# 01_Mcu.net
KiCad netlist of a schematic drawn in Altium Designer
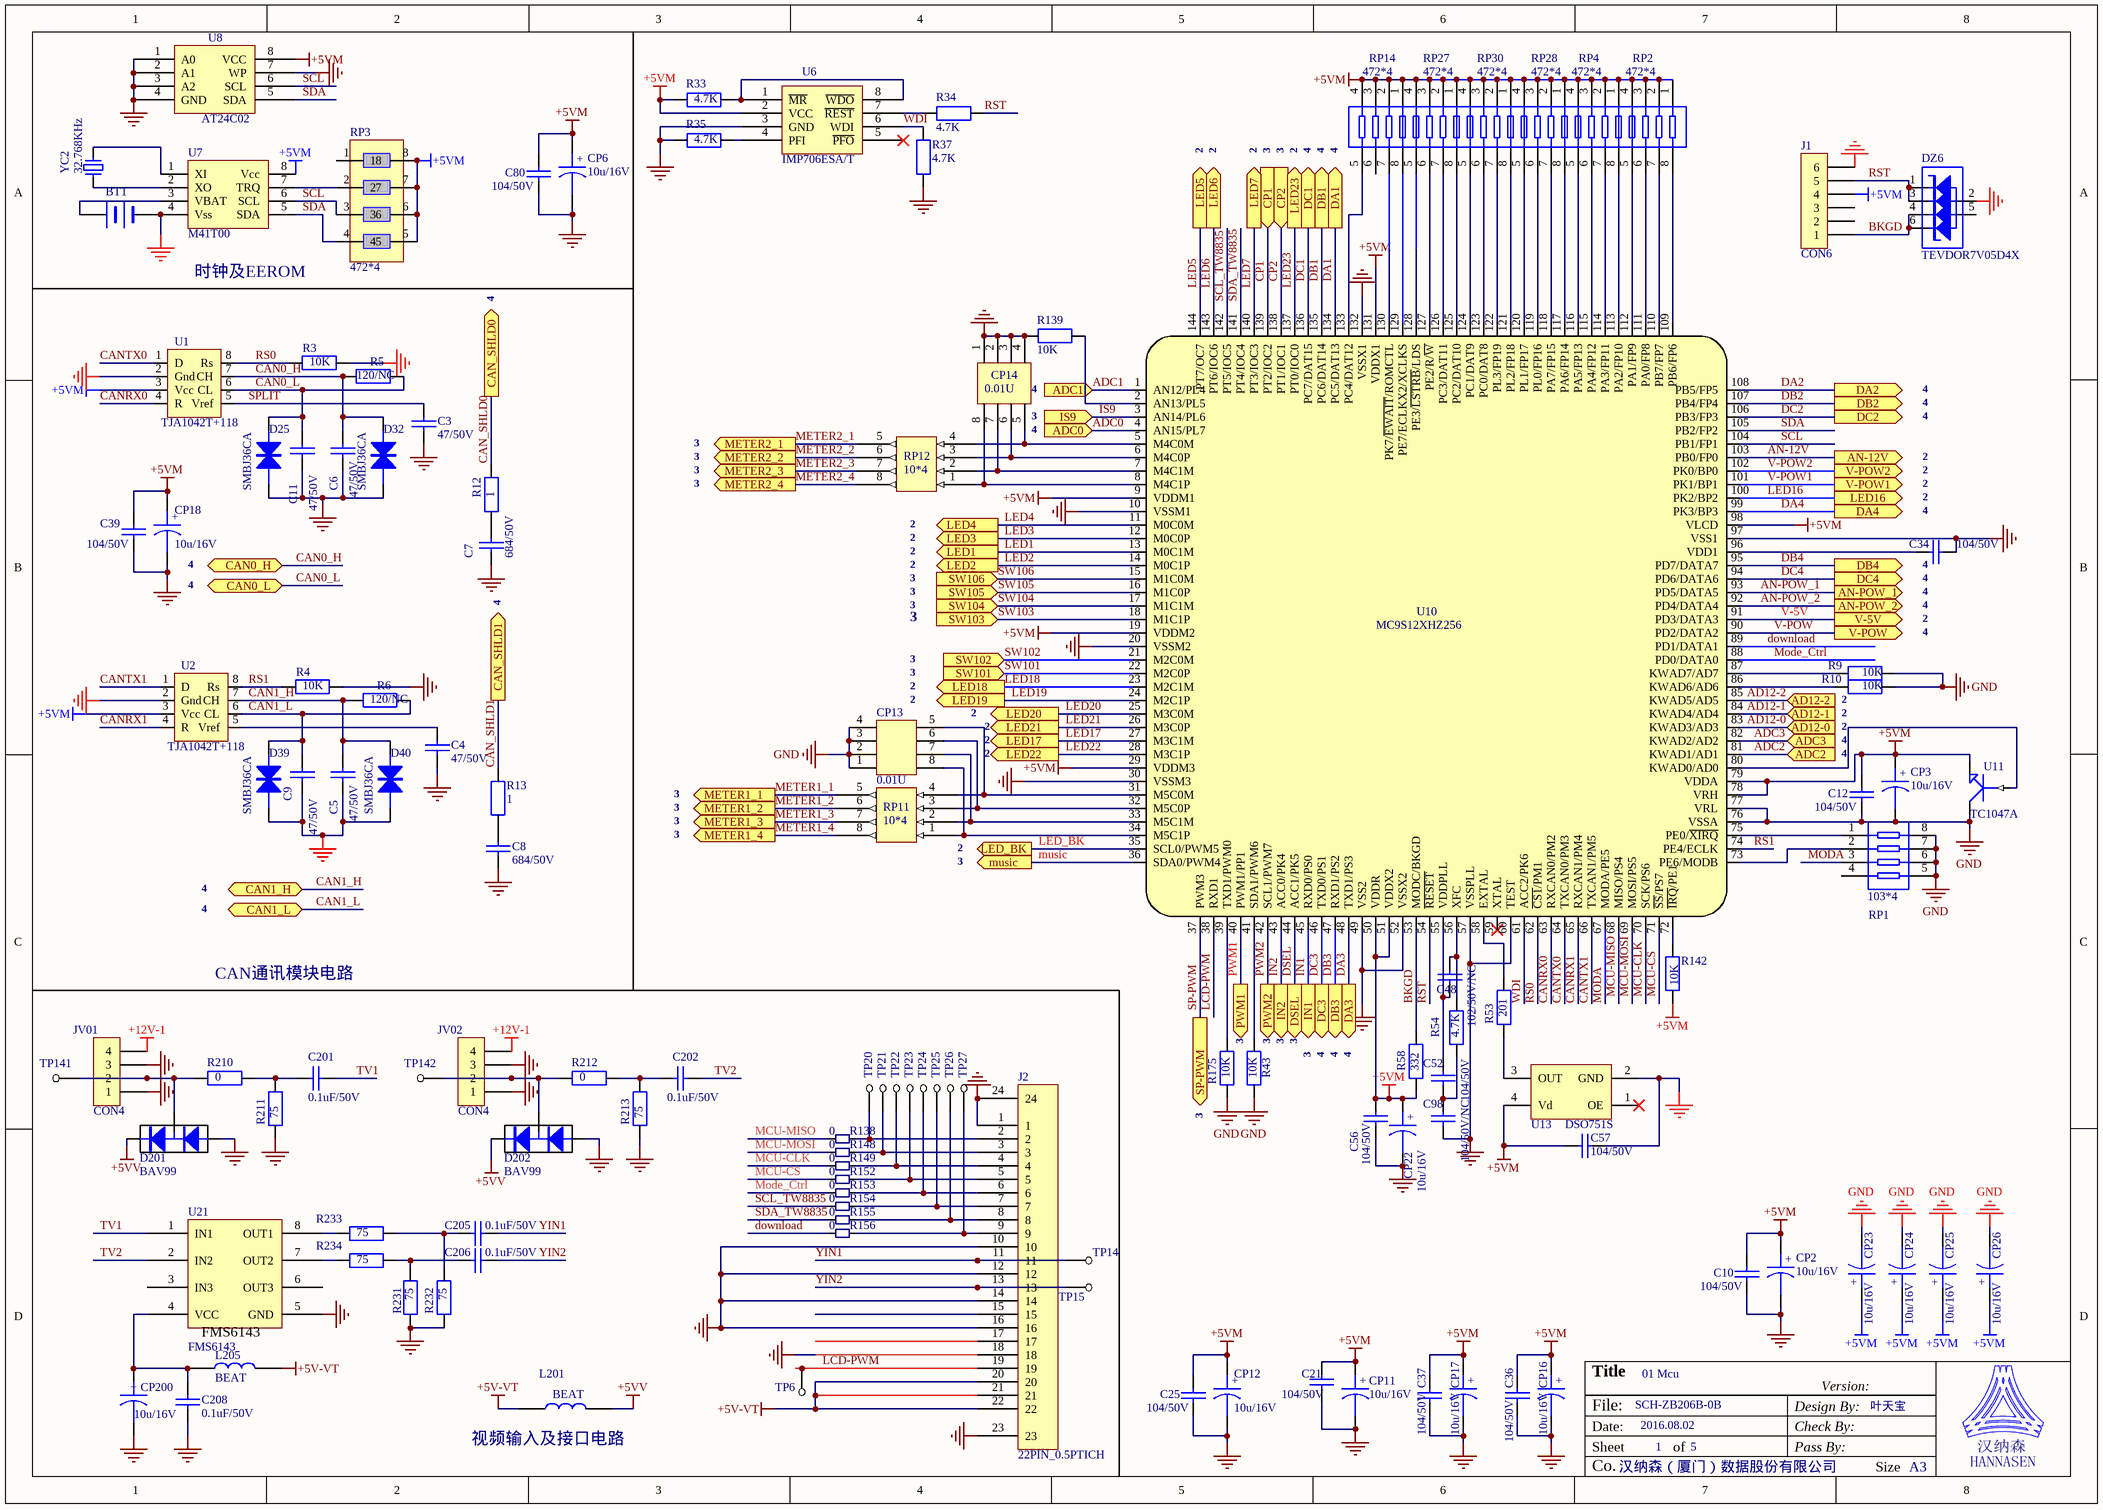
[diagram p0: 01 Mcu.SchDoc]

(export (version "E")
  (design (tool "Eeschema 10.0.6"))
  (components
    (comp (ref "BT1")
      (value "~")
      (footprint "Battery 3")
      (description "Battery")
      (libsource (lib "*") (part "BATTERY"))
    )
    (comp (ref "C3")
      (value "47/50V")
      (footprint "CR0805")
      (description "Capacitor")
      (libsource (lib "*") (part "CAP"))
    )
    (comp (ref "C4")
      (value "47/50V")
      (footprint "CR0805")
      (description "Capacitor")
      (libsource (lib "*") (part "CAP"))
    )
    (comp (ref "C5")
      (value "47/50V")
      (footprint "CR0805")
      (description "Capacitor")
      (libsource (lib "*") (part "CAP"))
    )
    (comp (ref "C6")
      (value "47/50V")
      (footprint "CR0805")
      (description "Capacitor")
      (libsource (lib "*") (part "CAP"))
    )
    (comp (ref "C7")
      (value "684/50V")
      (footprint "CR1206")
      (description "Capacitor")
      (libsource (lib "*") (part "CAP"))
    )
    (comp (ref "C8")
      (value "684/50V")
      (footprint "CR1206")
      (description "Capacitor")
      (libsource (lib "*") (part "CAP"))
    )
    (comp (ref "C9")
      (value "47/50V")
      (footprint "CR0805")
      (description "Capacitor")
      (libsource (lib "*") (part "CAP"))
    )
    (comp (ref "C10")
      (value "104/50V")
      (footprint "CR0805")
      (description "Capacitor")
      (libsource (lib "*") (part "CAP"))
    )
    (comp (ref "C11")
      (value "47/50V")
      (footprint "CR0805")
      (description "Capacitor")
      (libsource (lib "*") (part "CAP"))
    )
    (comp (ref "C12")
      (value "104/50V")
      (footprint "CR0805")
      (description "Capacitor")
      (libsource (lib "*") (part "CAP"))
    )
    (comp (ref "C21")
      (value "104/50V")
      (footprint "CR0805")
      (description "Capacitor")
      (libsource (lib "*") (part "CAP"))
    )
    (comp (ref "C25")
      (value "104/50V")
      (footprint "CR0805")
      (description "Capacitor")
      (libsource (lib "*") (part "CAP"))
    )
    (comp (ref "C34")
      (value "104/50V")
      (footprint "CR0805")
      (description "Capacitor")
      (libsource (lib "*") (part "CAP"))
    )
    (comp (ref "C36")
      (value "104/50V")
      (footprint "CR0805")
      (description "Capacitor")
      (libsource (lib "*") (part "CAP"))
    )
    (comp (ref "C37")
      (value "104/50V")
      (footprint "CR0805")
      (description "Capacitor")
      (libsource (lib "*") (part "CAP"))
    )
    (comp (ref "C39")
      (value "104/50V")
      (footprint "CR0805")
      (description "Capacitor")
      (libsource (lib "*") (part "CAP"))
    )
    (comp (ref "C48")
      (value "102/50V/NC")
      (footprint "CR0805")
      (description "Capacitor")
      (libsource (lib "*") (part "CAP"))
    )
    (comp (ref "C52")
      (value "104/50V")
      (footprint "CR0805")
      (description "Capacitor")
      (libsource (lib "*") (part "CAP"))
    )
    (comp (ref "C56")
      (value "104/50V")
      (footprint "CR0805")
      (description "Capacitor")
      (libsource (lib "*") (part "CAP"))
    )
    (comp (ref "C57")
      (value "104/50V")
      (footprint "CR0805")
      (description "Capacitor")
      (libsource (lib "*") (part "CAP"))
    )
    (comp (ref "C80")
      (value "104/50V")
      (footprint "CR0805")
      (description "Capacitor")
      (libsource (lib "*") (part "CAP"))
    )
    (comp (ref "C98")
      (value "104/50V/NC")
      (footprint "CR0805")
      (description "Capacitor")
      (libsource (lib "*") (part "CAP"))
    )
    (comp (ref "C201")
      (value "0.1uF/50V")
      (footprint "CR0805")
      (description "贴片电容")
      (libsource (lib "YDM-SQ-1SCH") (part "CAP"))
    )
    (comp (ref "C202")
      (value "0.1uF/50V")
      (footprint "CR0805")
      (description "贴片电容")
      (libsource (lib "YDM-SQ-1SCH") (part "CAP"))
    )
    (comp (ref "C205")
      (value "0.1uF/50V")
      (footprint "CR0805")
      (description "贴片电容")
      (libsource (lib "YDM-SQ-1SCH") (part "CAP"))
    )
    (comp (ref "C206")
      (value "0.1uF/50V")
      (footprint "CR0805")
      (description "贴片电容")
      (libsource (lib "YDM-SQ-1SCH") (part "CAP"))
    )
    (comp (ref "C208")
      (value "0.1uF/50V")
      (footprint "CR0805")
      (description "Capacitor")
      (libsource (lib "*") (part "CAP"))
    )
    (comp (ref "CP2")
      (value "10u/16V")
      (footprint "CE1206")
      (description "Capacitor")
      (libsource (lib "*") (part "CAPACITOR POL"))
    )
    (comp (ref "CP3")
      (value "10u/16V")
      (footprint "CE1206")
      (description "Capacitor")
      (libsource (lib "*") (part "CAPACITOR POL"))
    )
    (comp (ref "CP6")
      (value "10u/16V")
      (footprint "CE1206")
      (description "Capacitor")
      (libsource (lib "*") (part "CAPACITOR POL"))
    )
    (comp (ref "CP11")
      (value "10u/16V")
      (footprint "CE1206")
      (description "Capacitor")
      (libsource (lib "*") (part "CAPACITOR POL"))
    )
    (comp (ref "CP12")
      (value "10u/16V")
      (footprint "CE1206")
      (description "Capacitor")
      (libsource (lib "*") (part "CAPACITOR POL"))
    )
    (comp (ref "CP13") (value "0.01U") (footprint "C4") (libsource (lib "*") (part "RC_ARRAY")))
    (comp (ref "CP14") (value "0.01U") (footprint "C4") (libsource (lib "") (part "RC_ARRAY_1")))
    (comp (ref "CP16")
      (value "10u/16V")
      (footprint "CE1206")
      (description "Capacitor")
      (libsource (lib "*") (part "CAPACITOR POL"))
    )
    (comp (ref "CP17")
      (value "10u/16V")
      (footprint "CE1206")
      (description "Capacitor")
      (libsource (lib "*") (part "CAPACITOR POL"))
    )
    (comp (ref "CP18")
      (value "10u/16V")
      (footprint "CE1206")
      (description "Capacitor")
      (libsource (lib "*") (part "CAPACITOR POL"))
    )
    (comp (ref "CP22")
      (value "10u/16V")
      (footprint "CE1206")
      (description "Capacitor")
      (libsource (lib "*") (part "CAPACITOR POL"))
    )
    (comp (ref "CP23")
      (value "10u/16V")
      (footprint "CE1206")
      (description "Capacitor")
      (libsource (lib "*") (part "CAPACITOR POL"))
    )
    (comp (ref "CP24")
      (value "10u/16V")
      (footprint "CE1206")
      (description "Capacitor")
      (libsource (lib "*") (part "CAPACITOR POL"))
    )
    (comp (ref "CP25")
      (value "10u/16V")
      (footprint "CE1206")
      (description "Capacitor")
      (libsource (lib "*") (part "CAPACITOR POL"))
    )
    (comp (ref "CP26")
      (value "10u/16V")
      (footprint "CE1206")
      (description "Capacitor")
      (libsource (lib "*") (part "CAPACITOR POL"))
    )
    (comp (ref "CP200")
      (value "10u/16V")
      (footprint "CE1206")
      (description "Capacitor")
      (libsource (lib "") (part "CAPACITOR POL_1"))
    )
    (comp (ref "D25") (value "SMBJ36CA") (footprint "SMB-D") (libsource (lib "YDM-SQ-1SCH") (part "TVS")))
    (comp (ref "D32") (value "SMBJ36CA") (footprint "SMB-D") (libsource (lib "YDM-SQ-1SCH") (part "TVS")))
    (comp (ref "D39") (value "SMBJ36CA") (footprint "SMB-D") (libsource (lib "YDM-SQ-1SCH") (part "TVS")))
    (comp (ref "D40") (value "SMBJ36CA") (footprint "SMB-D") (libsource (lib "YDM-SQ-1SCH") (part "TVS")))
    (comp (ref "D201")
      (value "BAV99")
      (footprint "SOT23")
      (description "双二极管")
      (libsource (lib "YDM-SQ-1SCH") (part "BAV23S"))
    )
    (comp (ref "D202")
      (value "BAV99")
      (footprint "SOT23")
      (description "双二极管")
      (libsource (lib "YDM-SQ-1SCH") (part "BAV23S"))
    )
    (comp (ref "DZ6")
      (value "TEVDOR7V05D4X")
      (footprint "SOT-457")
      (description "二极管排")
      (libsource (lib "yibiaoschlib") (part "TEVDOR7V05D4X"))
    )
    (comp (ref "J1")
      (value "CON6")
      (footprint "DIP 2X3 2.54mm")
      (description "Connector")
      (libsource (lib "*") (part "CON6"))
    )
    (comp (ref "J2")
      (value "22PIN_0.5PTICH")
      (footprint "FPC-22P")
      (libsource (lib "yibiaoschlib") (part "22PIN_0.5PTICH"))
    )
    (comp (ref "JV01")
      (value "CON4")
      (footprint "DIP 1X4 2.5mm")
      (description "Connector")
      (libsource (lib "YDM-SQ-1SCH") (part "CON4"))
    )
    (comp (ref "JV02")
      (value "CON4")
      (footprint "DIP 1X4 2.5mm")
      (description "Connector")
      (libsource (lib "YDM-SQ-1SCH") (part "CON4"))
    )
    (comp (ref "L201") (value "BEAT") (footprint "CR0805") (libsource (lib "") (part "BEAT_1")))
    (comp (ref "L205") (value "BEAT") (footprint "CR0805") (libsource (lib "YDM-SQ-1SCH") (part "BEAT")))
    (comp (ref "R3")
      (value "10K")
      (footprint "CR0805")
      (description "贴片电阻")
      (libsource (lib "*") (part "RES"))
    )
    (comp (ref "R4")
      (value "10K")
      (footprint "CR0805")
      (description "贴片电阻")
      (libsource (lib "*") (part "RES"))
    )
    (comp (ref "R5")
      (value "120/NC")
      (footprint "CR0805")
      (description "贴片电阻")
      (libsource (lib "*") (part "RES"))
    )
    (comp (ref "R6")
      (value "120/NC")
      (footprint "CR0805")
      (description "贴片电阻")
      (libsource (lib "*") (part "RES"))
    )
    (comp (ref "R9")
      (value "10K")
      (footprint "CR0805")
      (description "贴片电阻")
      (libsource (lib "*") (part "RES"))
    )
    (comp (ref "R10")
      (value "10K")
      (footprint "CR0805")
      (description "贴片电阻")
      (libsource (lib "*") (part "RES"))
    )
    (comp (ref "R12")
      (value "1")
      (footprint "CR0805")
      (description "贴片电阻")
      (libsource (lib "*") (part "RES"))
    )
    (comp (ref "R13")
      (value "1")
      (footprint "CR0805")
      (description "贴片电阻")
      (libsource (lib "*") (part "RES"))
    )
    (comp (ref "R33")
      (value "4.7K")
      (footprint "CR0805")
      (description "贴片电阻")
      (libsource (lib "YDM-SQ-1SCH") (part "RES"))
    )
    (comp (ref "R34")
      (value "4.7K")
      (footprint "CR0805")
      (description "贴片电阻")
      (libsource (lib "*") (part "RES"))
    )
    (comp (ref "R35")
      (value "4.7K")
      (footprint "CR0805")
      (description "贴片电阻")
      (libsource (lib "YDM-SQ-1SCH") (part "RES"))
    )
    (comp (ref "R37")
      (value "4.7K")
      (footprint "CR0805")
      (description "贴片电阻")
      (libsource (lib "*") (part "RES"))
    )
    (comp (ref "R43")
      (value "10K")
      (footprint "CR0805")
      (description "贴片电阻")
      (libsource (lib "HNS-SCH") (part "RES"))
    )
    (comp (ref "R53")
      (value "201")
      (footprint "CR0805")
      (description "贴片电阻")
      (libsource (lib "*") (part "RES"))
    )
    (comp (ref "R54")
      (value "4.7K")
      (footprint "CR0805")
      (description "贴片电阻")
      (libsource (lib "*") (part "RES"))
    )
    (comp (ref "R58")
      (value "332")
      (footprint "CR0805")
      (description "贴片电阻")
      (libsource (lib "*") (part "RES"))
    )
    (comp (ref "R138")
      (value "0")
      (footprint "CR0805")
      (description "贴片电阻")
      (libsource (lib "YDM-SQ-1SCH") (part "Resister mini"))
    )
    (comp (ref "R139")
      (value "10K")
      (footprint "CR0805")
      (description "贴片电阻")
      (libsource (lib "*") (part "RES"))
    )
    (comp (ref "R142")
      (value "10K")
      (footprint "cr0805")
      (description "贴片电阻")
      (libsource (lib "*") (part "RES"))
    )
    (comp (ref "R148")
      (value "0")
      (footprint "CR0805")
      (description "贴片电阻")
      (libsource (lib "YDM-SQ-1SCH") (part "Resister mini"))
    )
    (comp (ref "R149")
      (value "0")
      (footprint "CR0805")
      (description "贴片电阻")
      (libsource (lib "YDM-SQ-1SCH") (part "Resister mini"))
    )
    (comp (ref "R152")
      (value "0")
      (footprint "CR0805")
      (description "贴片电阻")
      (libsource (lib "YDM-SQ-1SCH") (part "Resister mini"))
    )
    (comp (ref "R153")
      (value "0")
      (footprint "CR0805")
      (description "贴片电阻")
      (libsource (lib "YDM-SQ-1SCH") (part "Resister mini"))
    )
    (comp (ref "R154")
      (value "0")
      (footprint "CR0805")
      (description "贴片电阻")
      (libsource (lib "YDM-SQ-1SCH") (part "Resister mini"))
    )
    (comp (ref "R155")
      (value "0")
      (footprint "CR0805")
      (description "贴片电阻")
      (libsource (lib "YDM-SQ-1SCH") (part "Resister mini"))
    )
    (comp (ref "R156")
      (value "0")
      (footprint "CR0805")
      (description "贴片电阻")
      (libsource (lib "YDM-SQ-1SCH") (part "Resister mini"))
    )
    (comp (ref "R175")
      (value "10K")
      (footprint "CR0805")
      (description "贴片电阻")
      (libsource (lib "*") (part "RES"))
    )
    (comp (ref "R210")
      (value "0")
      (footprint "CR0805")
      (description "贴片电阻")
      (libsource (lib "YDM-SQ-1SCH") (part "RES"))
    )
    (comp (ref "R211")
      (value "75")
      (footprint "CR0805")
      (description "贴片电阻")
      (libsource (lib "YDM-SQ-1SCH") (part "RES"))
    )
    (comp (ref "R212")
      (value "0")
      (footprint "CR0805")
      (description "贴片电阻")
      (libsource (lib "YDM-SQ-1SCH") (part "RES"))
    )
    (comp (ref "R213")
      (value "75")
      (footprint "CR0805")
      (description "贴片电阻")
      (libsource (lib "YDM-SQ-1SCH") (part "RES"))
    )
    (comp (ref "R231")
      (value "75")
      (footprint "CR0805")
      (description "贴片电阻")
      (libsource (lib "YDM-SQ-1SCH") (part "RES"))
    )
    (comp (ref "R232")
      (value "75")
      (footprint "CR0805")
      (description "贴片电阻")
      (libsource (lib "YDM-SQ-1SCH") (part "RES"))
    )
    (comp (ref "R233")
      (value "75")
      (footprint "CR0805")
      (description "贴片电阻")
      (libsource (lib "YDM-SQ-1SCH") (part "RES"))
    )
    (comp (ref "R234")
      (value "75")
      (footprint "CR0805")
      (description "贴片电阻")
      (libsource (lib "YDM-SQ-1SCH") (part "RES"))
    )
    (comp (ref "RP1")
      (value "103*4")
      (footprint "R4")
      (description "贴片排阻")
      (libsource (lib "*") (part "R_LINE4"))
    )
    (comp (ref "RP2")
      (value "472*4")
      (footprint "R4")
      (description "贴片排阻")
      (libsource (lib "*") (part "R_LINE4"))
    )
    (comp (ref "RP3") (value "472*4") (footprint "R4") (libsource (lib "*") (part "R_ARRAY")))
    (comp (ref "RP4")
      (value "472*4")
      (footprint "R4")
      (description "贴片排阻")
      (libsource (lib "*") (part "R_LINE4"))
    )
    (comp (ref "RP11") (value "10*4") (footprint "R4") (libsource (lib "*") (part "R_PAI")))
    (comp (ref "RP12") (value "10*4") (footprint "R4") (libsource (lib "*") (part "R_PAI")))
    (comp (ref "RP14")
      (value "472*4")
      (footprint "R4")
      (description "贴片排阻")
      (libsource (lib "*") (part "R_LINE4"))
    )
    (comp (ref "RP27")
      (value "472*4")
      (footprint "R4")
      (description "贴片排阻")
      (libsource (lib "*") (part "R_LINE4"))
    )
    (comp (ref "RP28")
      (value "472*4")
      (footprint "R4")
      (description "贴片排阻")
      (libsource (lib "*") (part "R_LINE4"))
    )
    (comp (ref "RP30")
      (value "472*4")
      (footprint "R4")
      (description "贴片排阻")
      (libsource (lib "*") (part "R_LINE4"))
    )
    (comp (ref "TP6") (value "TP") (footprint "TP") (libsource (lib "YDM-SQ-1SCH") (part "TP")))
    (comp (ref "TP14") (value "TP") (footprint "TP") (libsource (lib "YDM-SQ-1SCH") (part "TP")))
    (comp (ref "TP15") (value "TP") (footprint "TP") (libsource (lib "YDM-SQ-1SCH") (part "TP")))
    (comp (ref "TP20") (value "TP") (footprint "TP") (libsource (lib "YDM-SQ-1SCH") (part "TP")))
    (comp (ref "TP21") (value "TP") (footprint "TP") (libsource (lib "YDM-SQ-1SCH") (part "TP")))
    (comp (ref "TP22") (value "TP") (footprint "TP") (libsource (lib "YDM-SQ-1SCH") (part "TP")))
    (comp (ref "TP23") (value "TP") (footprint "TP") (libsource (lib "YDM-SQ-1SCH") (part "TP")))
    (comp (ref "TP24") (value "TP") (footprint "TP") (libsource (lib "YDM-SQ-1SCH") (part "TP")))
    (comp (ref "TP25") (value "TP") (footprint "TP") (libsource (lib "YDM-SQ-1SCH") (part "TP")))
    (comp (ref "TP26") (value "TP") (footprint "TP") (libsource (lib "YDM-SQ-1SCH") (part "TP")))
    (comp (ref "TP27") (value "TP") (footprint "TP") (libsource (lib "YDM-SQ-1SCH") (part "TP")))
    (comp (ref "TP141") (value "~") (footprint "TP") (libsource (lib "YDM-SQ-1SCH") (part "TP")))
    (comp (ref "TP142") (value "~") (footprint "TP") (libsource (lib "YDM-SQ-1SCH") (part "TP")))
    (comp (ref "U1") (value "TJA1042T+118") (footprint "SO-8") (libsource (lib "*") (part "SN65HVD251")))
    (comp (ref "U2") (value "TJA1042T+118") (footprint "SO-8") (libsource (lib "*") (part "SN65HVD251")))
    (comp (ref "U6") (value "IMP706ESA/T") (footprint "SO-8") (libsource (lib "YDM-SQ-1SCH") (part "IMP706")))
    (comp (ref "U7")
      (value "M41T00")
      (footprint "SO-8")
      (description "IC")
      (libsource (lib "*") (part "M41T00"))
    )
    (comp (ref "U8")
      (value "AT24C02")
      (footprint "SO-8")
      (description "IC")
      (libsource (lib "*") (part "AT24C02"))
    )
    (comp (ref "U10")
      (value "MC9S12XHZ256")
      (footprint "LQFP-144")
      (libsource (lib "YDM-SQ-1SCH") (part "MC9S12XHZ256"))
    )
    (comp (ref "U11") (value "TC1047A") (footprint "SOT23") (libsource (lib "YDM-SQ-1SCH") (part "DTC143")))
    (comp (ref "U13") (value "DSO751S") (footprint "SMD-CYC") (libsource (lib "*") (part "POW_CRY")))
    (comp (ref "U21")
      (value "FMS6143")
      (footprint "SO-8")
      (description "IC-视频滤波")
      (libsource (lib "HNS-SCH") (part "FMS6143"))
    )
    (comp (ref "YC2")
      (value "32.768KHz")
      (footprint "SM CYC NX3215SA")
      (libsource (lib "*") (part "CRYSTAL0"))
    )
  )
  (nets
    (net (code "1") (name "+5V-VT") (class "Default")
      (node (ref "J2") (pin "20") (pinfunction "20_20") (pintype "passive"))
      (node (ref "J2") (pin "21") (pinfunction "21_21") (pintype "passive"))
      (node (ref "J2") (pin "22") (pinfunction "22_22") (pintype "passive"))
      (node (ref "L201") (pin "1") (pinfunction "1_1") (pintype "passive"))
      (node (ref "L205") (pin "1") (pinfunction "1_1") (pintype "passive"))
    )
    (net (code "2") (name "+5VM") (class "Default")
      (node (ref "C10") (pin "1") (pinfunction "1_1") (pintype "passive"))
      (node (ref "C12") (pin "1") (pinfunction "1_1") (pintype "passive"))
      (node (ref "C21") (pin "2") (pinfunction "2_2") (pintype "passive"))
      (node (ref "C25") (pin "1") (pinfunction "1_1") (pintype "passive"))
      (node (ref "C36") (pin "1") (pinfunction "1_1") (pintype "passive"))
      (node (ref "C37") (pin "1") (pinfunction "1_1") (pintype "passive"))
      (node (ref "C39") (pin "2") (pinfunction "2_2") (pintype "passive"))
      (node (ref "C56") (pin "1") (pinfunction "1_1") (pintype "passive"))
      (node (ref "C57") (pin "1") (pinfunction "1_1") (pintype "passive"))
      (node (ref "C80") (pin "1") (pinfunction "1_1") (pintype "passive"))
      (node (ref "CP11") (pin "1") (pinfunction "1_1") (pintype "passive"))
      (node (ref "CP12") (pin "1") (pinfunction "1_1") (pintype "passive"))
      (node (ref "CP16") (pin "1") (pinfunction "1_1") (pintype "passive"))
      (node (ref "CP17") (pin "1") (pinfunction "1_1") (pintype "passive"))
      (node (ref "CP18") (pin "1") (pinfunction "1_1") (pintype "passive"))
      (node (ref "CP2") (pin "1") (pinfunction "1_1") (pintype "passive"))
      (node (ref "CP22") (pin "1") (pinfunction "1_1") (pintype "passive"))
      (node (ref "CP23") (pin "1") (pinfunction "1_1") (pintype "passive"))
      (node (ref "CP24") (pin "1") (pinfunction "1_1") (pintype "passive"))
      (node (ref "CP25") (pin "1") (pinfunction "1_1") (pintype "passive"))
      (node (ref "CP26") (pin "1") (pinfunction "1_1") (pintype "passive"))
      (node (ref "CP3") (pin "1") (pinfunction "1_1") (pintype "passive"))
      (node (ref "CP6") (pin "1") (pinfunction "1_1") (pintype "passive"))
      (node (ref "J1") (pin "4") (pinfunction "4_4") (pintype "passive"))
      (node (ref "R142") (pin "2") (pinfunction "2_2") (pintype "passive"))
      (node (ref "R33") (pin "2") (pinfunction "2_2") (pintype "passive"))
      (node (ref "R58") (pin "1") (pinfunction "1_1") (pintype "passive"))
      (node (ref "RP14") (pin "1") (pinfunction "1_1") (pintype "passive"))
      (node (ref "RP14") (pin "2") (pinfunction "2_2") (pintype "passive"))
      (node (ref "RP14") (pin "3") (pinfunction "3_3") (pintype "passive"))
      (node (ref "RP14") (pin "4") (pinfunction "4_4") (pintype "passive"))
      (node (ref "RP2") (pin "1") (pinfunction "1_1") (pintype "passive"))
      (node (ref "RP2") (pin "2") (pinfunction "2_2") (pintype "passive"))
      (node (ref "RP2") (pin "3") (pinfunction "3_3") (pintype "passive"))
      (node (ref "RP2") (pin "4") (pinfunction "4_4") (pintype "passive"))
      (node (ref "RP27") (pin "1") (pinfunction "1_1") (pintype "passive"))
      (node (ref "RP27") (pin "2") (pinfunction "2_2") (pintype "passive"))
      (node (ref "RP27") (pin "3") (pinfunction "3_3") (pintype "passive"))
      (node (ref "RP27") (pin "4") (pinfunction "4_4") (pintype "passive"))
      (node (ref "RP28") (pin "1") (pinfunction "1_1") (pintype "passive"))
      (node (ref "RP28") (pin "2") (pinfunction "2_2") (pintype "passive"))
      (node (ref "RP28") (pin "3") (pinfunction "3_3") (pintype "passive"))
      (node (ref "RP28") (pin "4") (pinfunction "4_4") (pintype "passive"))
      (node (ref "RP3") (pin "5") (pinfunction "5_5") (pintype "passive"))
      (node (ref "RP3") (pin "6") (pinfunction "6_6") (pintype "passive"))
      (node (ref "RP3") (pin "7") (pinfunction "7_7") (pintype "passive"))
      (node (ref "RP3") (pin "8") (pinfunction "8_8") (pintype "passive"))
      (node (ref "RP30") (pin "1") (pinfunction "1_1") (pintype "passive"))
      (node (ref "RP30") (pin "2") (pinfunction "2_2") (pintype "passive"))
      (node (ref "RP30") (pin "3") (pinfunction "3_3") (pintype "passive"))
      (node (ref "RP30") (pin "4") (pinfunction "4_4") (pintype "passive"))
      (node (ref "RP4") (pin "1") (pinfunction "1_1") (pintype "passive"))
      (node (ref "RP4") (pin "2") (pinfunction "2_2") (pintype "passive"))
      (node (ref "RP4") (pin "3") (pinfunction "3_3") (pintype "passive"))
      (node (ref "RP4") (pin "4") (pinfunction "4_4") (pintype "passive"))
      (node (ref "U1") (pin "3") (pinfunction "Vcc_3") (pintype "passive"))
      (node (ref "U10") (pin "131") (pinfunction "VDDX1_131") (pintype "passive"))
      (node (ref "U10") (pin "19") (pinfunction "VDDM2_19") (pintype "passive"))
      (node (ref "U10") (pin "29") (pinfunction "VDDM3_29") (pintype "passive"))
      (node (ref "U10") (pin "50") (pinfunction "VDDR_50") (pintype "passive"))
      (node (ref "U10") (pin "51") (pinfunction "VDDX2_51") (pintype "passive"))
      (node (ref "U10") (pin "78") (pinfunction "VRH_78") (pintype "passive"))
      (node (ref "U10") (pin "79") (pinfunction "VDDA_79") (pintype "passive"))
      (node (ref "U10") (pin "9") (pinfunction "VDDM1_9") (pintype "passive"))
      (node (ref "U10") (pin "98") (pinfunction "VLCD_98") (pintype "passive"))
      (node (ref "U11") (pin "1") (pinfunction "E_1") (pintype "passive"))
      (node (ref "U13") (pin "4") (pinfunction "Vd_4") (pintype "passive"))
      (node (ref "U2") (pin "3") (pinfunction "Vcc_3") (pintype "passive"))
      (node (ref "U6") (pin "2") (pinfunction "VCC_2") (pintype "passive"))
      (node (ref "U7") (pin "8") (pinfunction "Vcc_8") (pintype "passive"))
      (node (ref "U8") (pin "8") (pinfunction "VCC_8") (pintype "passive"))
    )
    (net (code "3") (name "+5VV") (class "Default")
      (node (ref "D201") (pin "2") (pintype "passive"))
      (node (ref "D202") (pin "2") (pintype "passive"))
      (node (ref "L201") (pin "2") (pinfunction "2_2") (pintype "passive"))
    )
    (net (code "4") (name "+12V-1") (class "Default")
      (node (ref "JV01") (pin "4") (pinfunction "4_4") (pintype "passive"))
      (node (ref "JV02") (pin "4") (pinfunction "4_4") (pintype "passive"))
    )
    (net (code "6") (name "/AD12-0") (class "Default")
      (node (ref "U10") (pin "83") (pinfunction "KWAD3/AD3_83") (pintype "passive"))
    )
    (net (code "7") (name "/AD12-1") (class "Default")
      (node (ref "U10") (pin "84") (pinfunction "KWAD4/AD4_84") (pintype "passive"))
    )
    (net (code "8") (name "/AD12-2") (class "Default")
      (node (ref "U10") (pin "85") (pinfunction "KWAD5/AD5_85") (pintype "passive"))
    )
    (net (code "9") (name "/ADC0") (class "Default")
      (node (ref "U10") (pin "4") (pinfunction "AN15/PL7_4") (pintype "passive"))
    )
    (net (code "10") (name "/ADC1") (class "Default")
      (node (ref "U10") (pin "1") (pinfunction "AN12/PL4_1") (pintype "passive"))
    )
    (net (code "11") (name "/ADC2") (class "Default")
      (node (ref "U10") (pin "81") (pinfunction "KWAD1/AD1_81") (pintype "passive"))
    )
    (net (code "12") (name "/ADC3") (class "Default")
      (node (ref "U10") (pin "82") (pinfunction "KWAD2/AD2_82") (pintype "passive"))
    )
    (net (code "13") (name "/AN-12V") (class "Default")
      (node (ref "U10") (pin "103") (pinfunction "PB0/FP0_103") (pintype "passive"))
    )
    (net (code "14") (name "/AN-POW_1") (class "Default")
      (node (ref "U10") (pin "93") (pinfunction "PD5/DATA5_93") (pintype "passive"))
    )
    (net (code "15") (name "/AN-POW_2") (class "Default")
      (node (ref "U10") (pin "92") (pinfunction "PD4/DATA4_92") (pintype "passive"))
    )
    (net (code "16") (name "/BKGD") (class "Default")
      (node (ref "DZ6") (pin "4") (pintype "passive"))
      (node (ref "DZ6") (pin "6") (pintype "passive"))
      (node (ref "J1") (pin "1") (pinfunction "1_1") (pintype "passive"))
      (node (ref "R58") (pin "2") (pinfunction "2_2") (pintype "passive"))
      (node (ref "U10") (pin "53") (pinfunction "MODC/BKGD_53") (pintype "passive"))
    )
    (net (code "17") (name "/CAN0_H") (class "Default")
      (node (ref "C6") (pin "2") (pinfunction "2_2") (pintype "passive"))
      (node (ref "D32") (pin "2") (pinfunction "2_2") (pintype "passive"))
      (node (ref "R5") (pin "2") (pinfunction "2_2") (pintype "passive"))
      (node (ref "U1") (pin "7") (pinfunction "CH_7") (pintype "passive"))
    )
    (net (code "18") (name "/CAN0_L") (class "Default")
      (node (ref "C11") (pin "2") (pinfunction "2_2") (pintype "passive"))
      (node (ref "D25") (pin "2") (pinfunction "2_2") (pintype "passive"))
      (node (ref "R5") (pin "1") (pinfunction "1_1") (pintype "passive"))
      (node (ref "U1") (pin "6") (pinfunction "CL_6") (pintype "passive"))
    )
    (net (code "19") (name "/CAN1_H") (class "Default")
      (node (ref "C5") (pin "2") (pinfunction "2_2") (pintype "passive"))
      (node (ref "D40") (pin "2") (pinfunction "2_2") (pintype "passive"))
      (node (ref "R6") (pin "2") (pinfunction "2_2") (pintype "passive"))
      (node (ref "U2") (pin "7") (pinfunction "CH_7") (pintype "passive"))
    )
    (net (code "20") (name "/CAN1_L") (class "Default")
      (node (ref "C9") (pin "2") (pinfunction "2_2") (pintype "passive"))
      (node (ref "D39") (pin "2") (pinfunction "2_2") (pintype "passive"))
      (node (ref "R6") (pin "1") (pinfunction "1_1") (pintype "passive"))
      (node (ref "U2") (pin "6") (pinfunction "CL_6") (pintype "passive"))
    )
    (net (code "21") (name "/CANRX0") (class "Default")
      (node (ref "U1") (pin "4") (pinfunction "R_4") (pintype "passive"))
      (node (ref "U10") (pin "63") (pinfunction "RXCAN0/PM2_63") (pintype "passive"))
    )
    (net (code "22") (name "/CANRX1") (class "Default")
      (node (ref "U10") (pin "65") (pinfunction "RXCAN1/PM4_65") (pintype "passive"))
      (node (ref "U2") (pin "4") (pinfunction "R_4") (pintype "passive"))
    )
    (net (code "23") (name "/CANTX0") (class "Default")
      (node (ref "U1") (pin "1") (pinfunction "D_1") (pintype "passive"))
      (node (ref "U10") (pin "64") (pinfunction "TXCAN0/PM3_64") (pintype "passive"))
    )
    (net (code "24") (name "/CANTX1") (class "Default")
      (node (ref "U10") (pin "66") (pinfunction "TXCAN1/PM5_66") (pintype "passive"))
      (node (ref "U2") (pin "1") (pinfunction "D_1") (pintype "passive"))
    )
    (net (code "25") (name "/CAN_SHLD0") (class "Default")
      (node (ref "R12") (pin "2") (pinfunction "2_2") (pintype "passive"))
    )
    (net (code "26") (name "/CAN_SHLD1") (class "Default")
      (node (ref "R13") (pin "2") (pinfunction "2_2") (pintype "passive"))
    )
    (net (code "27") (name "/CP1") (class "Default")
      (node (ref "U10") (pin "139") (pinfunction "PT2/IOC2_139") (pintype "passive"))
    )
    (net (code "28") (name "/CP2") (class "Default")
      (node (ref "U10") (pin "138") (pinfunction "PT1/IOC1_138") (pintype "passive"))
    )
    (net (code "29") (name "/DA1") (class "Default")
      (node (ref "U10") (pin "134") (pinfunction "PC5/DAT13_134") (pintype "passive"))
    )
    (net (code "30") (name "/DA2") (class "Default")
      (node (ref "U10") (pin "108") (pinfunction "PB5/FP5_108") (pintype "passive"))
    )
    (net (code "31") (name "/DA3") (class "Default")
      (node (ref "U10") (pin "48") (pinfunction "TXD1/PS3_48") (pintype "passive"))
    )
    (net (code "32") (name "/DA4") (class "Default")
      (node (ref "U10") (pin "99") (pinfunction "PK3/BP3_99") (pintype "passive"))
    )
    (net (code "33") (name "/DB1") (class "Default")
      (node (ref "U10") (pin "135") (pinfunction "PC6/DAT14_135") (pintype "passive"))
    )
    (net (code "34") (name "/DB2") (class "Default")
      (node (ref "U10") (pin "107") (pinfunction "PB4/FP4_107") (pintype "passive"))
    )
    (net (code "35") (name "/DB3") (class "Default")
      (node (ref "U10") (pin "47") (pinfunction "RXD1/PS2_47") (pintype "passive"))
    )
    (net (code "36") (name "/DB4") (class "Default")
      (node (ref "U10") (pin "95") (pinfunction "PD7/DATA7_95") (pintype "passive"))
    )
    (net (code "37") (name "/DC1") (class "Default")
      (node (ref "U10") (pin "136") (pinfunction "PC7/DAT15_136") (pintype "passive"))
    )
    (net (code "38") (name "/DC2") (class "Default")
      (node (ref "U10") (pin "106") (pinfunction "PB3/FP3_106") (pintype "passive"))
    )
    (net (code "39") (name "/DC3") (class "Default")
      (node (ref "U10") (pin "46") (pinfunction "TXD0/PS1_46") (pintype "passive"))
    )
    (net (code "40") (name "/DC4") (class "Default")
      (node (ref "U10") (pin "94") (pinfunction "PD6/DATA6_94") (pintype "passive"))
    )
    (net (code "41") (name "/DSEL") (class "Default")
      (node (ref "U10") (pin "44") (pinfunction "ACC1/PK5_44") (pintype "passive"))
    )
    (net (code "42") (name "/IN1") (class "Default")
      (node (ref "U10") (pin "45") (pinfunction "RXD0/PS0_45") (pintype "passive"))
    )
    (net (code "43") (name "/IN2") (class "Default")
      (node (ref "U10") (pin "43") (pinfunction "ACC0/PK4_43") (pintype "passive"))
    )
    (net (code "44") (name "/IS9") (class "Default")
      (node (ref "U10") (pin "3") (pinfunction "AN14/PL6_3") (pintype "passive"))
    )
    (net (code "45") (name "/LCD-PWM") (class "Default")
      (node (ref "J2") (pin "19") (pinfunction "19_19") (pintype "passive"))
      (node (ref "TP6") (pin "1") (pinfunction "1_1") (pintype "passive"))
      (node (ref "U10") (pin "38") (pinfunction "RXD1_38") (pintype "passive"))
    )
    (net (code "46") (name "/LED1") (class "Default")
      (node (ref "U10") (pin "13") (pinfunction "M0C1M_13") (pintype "passive"))
    )
    (net (code "47") (name "/LED2") (class "Default")
      (node (ref "U10") (pin "14") (pinfunction "M0C1P_14") (pintype "passive"))
    )
    (net (code "48") (name "/LED3") (class "Default")
      (node (ref "U10") (pin "12") (pinfunction "M0C0P_12") (pintype "passive"))
    )
    (net (code "49") (name "/LED4") (class "Default")
      (node (ref "U10") (pin "11") (pinfunction "M0C0M_11") (pintype "passive"))
    )
    (net (code "50") (name "/LED5") (class "Default")
      (node (ref "U10") (pin "144") (pinfunction "PT7/OC7_144") (pintype "passive"))
    )
    (net (code "51") (name "/LED6") (class "Default")
      (node (ref "U10") (pin "143") (pinfunction "PT6/IOC6_143") (pintype "passive"))
    )
    (net (code "52") (name "/LED7") (class "Default")
      (node (ref "U10") (pin "140") (pinfunction "PT3/IOC3_140") (pintype "passive"))
    )
    (net (code "53") (name "/LED16") (class "Default")
      (node (ref "U10") (pin "100") (pinfunction "PK2/BP2_100") (pintype "passive"))
    )
    (net (code "54") (name "/LED17") (class "Default")
      (node (ref "U10") (pin "27") (pinfunction "M3C1M_27") (pintype "passive"))
    )
    (net (code "55") (name "/LED18") (class "Default")
      (node (ref "U10") (pin "23") (pinfunction "M2C1M_23") (pintype "passive"))
    )
    (net (code "56") (name "/LED19") (class "Default")
      (node (ref "U10") (pin "24") (pinfunction "M2C1P_24") (pintype "passive"))
    )
    (net (code "57") (name "/LED20") (class "Default")
      (node (ref "U10") (pin "25") (pinfunction "M3C0M_25") (pintype "passive"))
    )
    (net (code "58") (name "/LED21") (class "Default")
      (node (ref "U10") (pin "26") (pinfunction "M3C0P_26") (pintype "passive"))
    )
    (net (code "59") (name "/LED22") (class "Default")
      (node (ref "U10") (pin "28") (pinfunction "M3C1P_28") (pintype "passive"))
    )
    (net (code "60") (name "/LED23") (class "Default")
      (node (ref "U10") (pin "137") (pinfunction "PT0/IOC0_137") (pintype "passive"))
    )
    (net (code "61") (name "/LED_BK") (class "Default")
      (node (ref "U10") (pin "35") (pinfunction "SCL0/PWM5_35") (pintype "passive"))
    )
    (net (code "62") (name "/MCU-CLK") (class "Default")
      (node (ref "R149") (pin "2") (pinfunction "2_2") (pintype "passive"))
      (node (ref "U10") (pin "70") (pinfunction "SCK/PS6_70") (pintype "passive"))
    )
    (net (code "63") (name "/MCU-CS") (class "Default")
      (node (ref "R152") (pin "2") (pinfunction "2_2") (pintype "passive"))
      (node (ref "U10") (pin "71") (pinfunction "~{SS}/PS7_71") (pintype "passive"))
    )
    (net (code "64") (name "/MCU-MISO") (class "Default")
      (node (ref "R138") (pin "2") (pinfunction "2_2") (pintype "passive"))
      (node (ref "U10") (pin "68") (pinfunction "MISO/PS4_68") (pintype "passive"))
    )
    (net (code "65") (name "/MCU-MOSI") (class "Default")
      (node (ref "R148") (pin "2") (pinfunction "2_2") (pintype "passive"))
      (node (ref "U10") (pin "69") (pinfunction "MOSI/PS5_69") (pintype "passive"))
    )
    (net (code "66") (name "/METER1_1") (class "Default")
      (node (ref "RP11") (pin "5") (pinfunction "5_5") (pintype "output"))
    )
    (net (code "67") (name "/METER1_2") (class "Default")
      (node (ref "RP11") (pin "6") (pinfunction "6_6") (pintype "output"))
    )
    (net (code "68") (name "/METER1_3") (class "Default")
      (node (ref "RP11") (pin "7") (pinfunction "7_7") (pintype "output"))
    )
    (net (code "69") (name "/METER1_4") (class "Default")
      (node (ref "RP11") (pin "8") (pinfunction "8_8") (pintype "output"))
    )
    (net (code "70") (name "/METER2_1") (class "Default")
      (node (ref "RP12") (pin "5") (pinfunction "5_5") (pintype "output"))
    )
    (net (code "71") (name "/METER2_2") (class "Default")
      (node (ref "RP12") (pin "6") (pinfunction "6_6") (pintype "output"))
    )
    (net (code "72") (name "/METER2_3") (class "Default")
      (node (ref "RP12") (pin "7") (pinfunction "7_7") (pintype "output"))
    )
    (net (code "73") (name "/METER2_4") (class "Default")
      (node (ref "RP12") (pin "8") (pinfunction "8_8") (pintype "output"))
    )
    (net (code "74") (name "/MODA") (class "Default")
      (node (ref "RP1") (pin "3") (pinfunction "3_3") (pintype "passive"))
      (node (ref "U10") (pin "67") (pinfunction "MODA/PE5_67") (pintype "passive"))
    )
    (net (code "75") (name "/Mode_Ctrl") (class "Default")
      (node (ref "R153") (pin "2") (pinfunction "2_2") (pintype "passive"))
      (node (ref "U10") (pin "88") (pinfunction "PD0/DATA0_88") (pintype "passive"))
    )
    (net (code "76") (name "/PWM1") (class "Default")
      (node (ref "U10") (pin "40") (pinfunction "PWM1/PP1_40") (pintype "passive"))
    )
    (net (code "77") (name "/PWM2") (class "Default")
      (node (ref "U10") (pin "42") (pinfunction "SCL1/PWM7_42") (pintype "passive"))
    )
    (net (code "78") (name "/RS0") (class "Default")
      (node (ref "R3") (pin "1") (pinfunction "1_1") (pintype "passive"))
      (node (ref "U1") (pin "8") (pinfunction "Rs_8") (pintype "passive"))
      (node (ref "U10") (pin "62") (pinfunction "~{CS1}/PM1_62") (pintype "passive"))
    )
    (net (code "79") (name "/RS1") (class "Default")
      (node (ref "R4") (pin "1") (pinfunction "1_1") (pintype "passive"))
      (node (ref "U10") (pin "74") (pinfunction "PE4/ECLK_74") (pintype "passive"))
      (node (ref "U2") (pin "8") (pinfunction "Rs_8") (pintype "passive"))
    )
    (net (code "80") (name "/RST") (class "Default")
      (node (ref "DZ6") (pin "1") (pintype "passive"))
      (node (ref "DZ6") (pin "3") (pintype "passive"))
      (node (ref "J1") (pin "5") (pinfunction "5_5") (pintype "passive"))
      (node (ref "R34") (pin "2") (pinfunction "2_2") (pintype "passive"))
      (node (ref "U10") (pin "54") (pinfunction "~{RESET}_54") (pintype "passive"))
    )
    (net (code "81") (name "/SCL") (class "Default")
      (node (ref "RP3") (pin "3") (pinfunction "3_3") (pintype "passive"))
      (node (ref "U10") (pin "104") (pinfunction "PB1/FP1_104") (pintype "passive"))
      (node (ref "U7") (pin "6") (pinfunction "SCL_6") (pintype "passive"))
      (node (ref "U8") (pin "6") (pinfunction "SCL_6") (pintype "passive"))
    )
    (net (code "82") (name "/SCL_TW8835") (class "Default")
      (node (ref "R154") (pin "2") (pinfunction "2_2") (pintype "passive"))
      (node (ref "U10") (pin "142") (pinfunction "PT5/IOC5_142") (pintype "passive"))
    )
    (net (code "83") (name "/SDA") (class "Default")
      (node (ref "RP3") (pin "4") (pinfunction "4_4") (pintype "passive"))
      (node (ref "U10") (pin "105") (pinfunction "PB2/FP2_105") (pintype "passive"))
      (node (ref "U7") (pin "5") (pinfunction "SDA_5") (pintype "passive"))
      (node (ref "U8") (pin "5") (pinfunction "SDA_5") (pintype "passive"))
    )
    (net (code "84") (name "/SDA_TW8835") (class "Default")
      (node (ref "R155") (pin "2") (pinfunction "2_2") (pintype "passive"))
      (node (ref "U10") (pin "141") (pinfunction "PT4/IOC4_141") (pintype "passive"))
    )
    (net (code "85") (name "/SP-PWM") (class "Default")
      (node (ref "U10") (pin "37") (pinfunction "PWM3_37") (pintype "passive"))
    )
    (net (code "86") (name "/SPLIT") (class "Default")
      (node (ref "C3") (pin "1") (pinfunction "1_1") (pintype "passive"))
      (node (ref "U1") (pin "5") (pinfunction "Vref_5") (pintype "passive"))
    )
    (net (code "87") (name "/SW101") (class "Default")
      (node (ref "U10") (pin "22") (pinfunction "M2C0P_22") (pintype "passive"))
    )
    (net (code "88") (name "/SW102") (class "Default")
      (node (ref "U10") (pin "21") (pinfunction "M2C0M_21") (pintype "passive"))
    )
    (net (code "89") (name "/SW103") (class "Default")
      (node (ref "U10") (pin "18") (pinfunction "M1C1P_18") (pintype "passive"))
    )
    (net (code "90") (name "/SW104") (class "Default")
      (node (ref "U10") (pin "17") (pinfunction "M1C1M_17") (pintype "passive"))
    )
    (net (code "91") (name "/SW105") (class "Default")
      (node (ref "U10") (pin "16") (pinfunction "M1C0P_16") (pintype "passive"))
    )
    (net (code "92") (name "/SW106") (class "Default")
      (node (ref "U10") (pin "15") (pinfunction "M1C0M_15") (pintype "passive"))
    )
    (net (code "93") (name "/TV1") (class "Default")
      (node (ref "C201") (pin "2") (pinfunction "2_2") (pintype "passive"))
      (node (ref "U21") (pin "1") (pinfunction "IN1_1") (pintype "passive"))
    )
    (net (code "94") (name "/TV2") (class "Default")
      (node (ref "C202") (pin "2") (pinfunction "2_2") (pintype "passive"))
      (node (ref "U21") (pin "2") (pinfunction "IN2_2") (pintype "passive"))
    )
    (net (code "95") (name "/V-5V") (class "Default")
      (node (ref "U10") (pin "91") (pinfunction "PD3/DATA3_91") (pintype "passive"))
    )
    (net (code "96") (name "/V-POW") (class "Default")
      (node (ref "U10") (pin "90") (pinfunction "PD2/DATA2_90") (pintype "passive"))
    )
    (net (code "97") (name "/V-POW1") (class "Default")
      (node (ref "U10") (pin "101") (pinfunction "PK1/BP1_101") (pintype "passive"))
    )
    (net (code "98") (name "/V-POW2") (class "Default")
      (node (ref "U10") (pin "102") (pinfunction "PK0/BP0_102") (pintype "passive"))
    )
    (net (code "99") (name "/WDI") (class "Default")
      (node (ref "R37") (pin "1") (pinfunction "1_1") (pintype "passive"))
      (node (ref "U10") (pin "61") (pinfunction "ACC2/PK6_61") (pintype "passive"))
      (node (ref "U6") (pin "6") (pinfunction "WDI_6") (pintype "passive"))
    )
    (net (code "100") (name "/YIN1") (class "Default")
      (node (ref "C205") (pin "2") (pinfunction "2_2") (pintype "passive"))
      (node (ref "J2") (pin "11") (pinfunction "11_11") (pintype "passive"))
      (node (ref "TP14") (pin "1") (pinfunction "1_1") (pintype "passive"))
    )
    (net (code "101") (name "/YIN2") (class "Default")
      (node (ref "C206") (pin "2") (pinfunction "2_2") (pintype "passive"))
      (node (ref "J2") (pin "13") (pinfunction "13_13") (pintype "passive"))
      (node (ref "TP15") (pin "1") (pinfunction "1_1") (pintype "passive"))
    )
    (net (code "102") (name "/download") (class "Default")
      (node (ref "R156") (pin "2") (pinfunction "2_2") (pintype "passive"))
      (node (ref "U10") (pin "89") (pinfunction "PD1/DATA1_89") (pintype "passive"))
    )
    (net (code "103") (name "/music") (class "Default")
      (node (ref "U10") (pin "36") (pinfunction "SDA0/PWM4_36") (pintype "passive"))
    )
    (net (code "104") (name "GND") (class "Default")
      (node (ref "BT1") (pin "2") (pinfunction "-_2") (pintype "passive"))
      (node (ref "C10") (pin "2") (pinfunction "2_2") (pintype "passive"))
      (node (ref "C11") (pin "1") (pinfunction "1_1") (pintype "passive"))
      (node (ref "C12") (pin "2") (pinfunction "2_2") (pintype "passive"))
      (node (ref "C208") (pin "2") (pinfunction "2_2") (pintype "passive"))
      (node (ref "C21") (pin "1") (pinfunction "1_1") (pintype "passive"))
      (node (ref "C25") (pin "2") (pinfunction "2_2") (pintype "passive"))
      (node (ref "C3") (pin "2") (pinfunction "2_2") (pintype "passive"))
      (node (ref "C34") (pin "2") (pinfunction "2_2") (pintype "passive"))
      (node (ref "C36") (pin "2") (pinfunction "2_2") (pintype "passive"))
      (node (ref "C37") (pin "2") (pinfunction "2_2") (pintype "passive"))
      (node (ref "C39") (pin "1") (pinfunction "1_1") (pintype "passive"))
      (node (ref "C4") (pin "2") (pinfunction "2_2") (pintype "passive"))
      (node (ref "C5") (pin "1") (pinfunction "1_1") (pintype "passive"))
      (node (ref "C56") (pin "2") (pinfunction "2_2") (pintype "passive"))
      (node (ref "C57") (pin "2") (pinfunction "2_2") (pintype "passive"))
      (node (ref "C6") (pin "1") (pinfunction "1_1") (pintype "passive"))
      (node (ref "C7") (pin "2") (pinfunction "2_2") (pintype "passive"))
      (node (ref "C8") (pin "2") (pinfunction "2_2") (pintype "passive"))
      (node (ref "C80") (pin "2") (pinfunction "2_2") (pintype "passive"))
      (node (ref "C9") (pin "1") (pinfunction "1_1") (pintype "passive"))
      (node (ref "C98") (pin "2") (pinfunction "2_2") (pintype "passive"))
      (node (ref "CP11") (pin "2") (pinfunction "2_2") (pintype "passive"))
      (node (ref "CP12") (pin "2") (pinfunction "2_2") (pintype "passive"))
      (node (ref "CP13") (pin "1") (pinfunction "1_1") (pintype "passive"))
      (node (ref "CP13") (pin "2") (pinfunction "2_2") (pintype "passive"))
      (node (ref "CP13") (pin "3") (pinfunction "3_3") (pintype "passive"))
      (node (ref "CP13") (pin "4") (pinfunction "4_4") (pintype "passive"))
      (node (ref "CP14") (pin "1") (pinfunction "1_1") (pintype "passive"))
      (node (ref "CP14") (pin "2") (pinfunction "2_2") (pintype "passive"))
      (node (ref "CP14") (pin "3") (pinfunction "3_3") (pintype "passive"))
      (node (ref "CP14") (pin "4") (pinfunction "4_4") (pintype "passive"))
      (node (ref "CP16") (pin "2") (pinfunction "2_2") (pintype "passive"))
      (node (ref "CP17") (pin "2") (pinfunction "2_2") (pintype "passive"))
      (node (ref "CP18") (pin "2") (pinfunction "2_2") (pintype "passive"))
      (node (ref "CP2") (pin "2") (pinfunction "2_2") (pintype "passive"))
      (node (ref "CP200") (pin "2") (pinfunction "2_2") (pintype "passive"))
      (node (ref "CP22") (pin "2") (pinfunction "2_2") (pintype "passive"))
      (node (ref "CP23") (pin "2") (pinfunction "2_2") (pintype "passive"))
      (node (ref "CP24") (pin "2") (pinfunction "2_2") (pintype "passive"))
      (node (ref "CP25") (pin "2") (pinfunction "2_2") (pintype "passive"))
      (node (ref "CP26") (pin "2") (pinfunction "2_2") (pintype "passive"))
      (node (ref "CP3") (pin "2") (pinfunction "2_2") (pintype "passive"))
      (node (ref "CP6") (pin "2") (pinfunction "2_2") (pintype "passive"))
      (node (ref "D201") (pin "1") (pintype "passive"))
      (node (ref "D202") (pin "1") (pintype "passive"))
      (node (ref "D25") (pin "1") (pinfunction "1_1") (pintype "passive"))
      (node (ref "D32") (pin "1") (pinfunction "1_1") (pintype "passive"))
      (node (ref "D39") (pin "1") (pinfunction "1_1") (pintype "passive"))
      (node (ref "D40") (pin "1") (pinfunction "1_1") (pintype "passive"))
      (node (ref "DZ6") (pin "2") (pintype "passive"))
      (node (ref "J1") (pin "6") (pinfunction "6_6") (pintype "passive"))
      (node (ref "J2") (pin "1") (pinfunction "1_1") (pintype "passive"))
      (node (ref "J2") (pin "10") (pinfunction "10_10") (pintype "passive"))
      (node (ref "J2") (pin "12") (pinfunction "12_12") (pintype "passive"))
      (node (ref "J2") (pin "14") (pinfunction "14_14") (pintype "passive"))
      (node (ref "J2") (pin "16") (pinfunction "16_16") (pintype "passive"))
      (node (ref "J2") (pin "18") (pinfunction "18_18") (pintype "passive"))
      (node (ref "J2") (pin "23") (pinfunction "23_23") (pintype "passive"))
      (node (ref "J2") (pin "24") (pinfunction "24_24") (pintype "passive"))
      (node (ref "JV01") (pin "1") (pinfunction "1_1") (pintype "passive"))
      (node (ref "JV01") (pin "3") (pinfunction "3_3") (pintype "passive"))
      (node (ref "JV02") (pin "1") (pinfunction "1_1") (pintype "passive"))
      (node (ref "JV02") (pin "3") (pinfunction "3_3") (pintype "passive"))
      (node (ref "R10") (pin "2") (pinfunction "2_2") (pintype "passive"))
      (node (ref "R139") (pin "1") (pinfunction "1_1") (pintype "passive"))
      (node (ref "R175") (pin "2") (pinfunction "2_2") (pintype "passive"))
      (node (ref "R211") (pin "2") (pinfunction "2_2") (pintype "passive"))
      (node (ref "R213") (pin "2") (pinfunction "2_2") (pintype "passive"))
      (node (ref "R231") (pin "2") (pinfunction "2_2") (pintype "passive"))
      (node (ref "R232") (pin "2") (pinfunction "2_2") (pintype "passive"))
      (node (ref "R3") (pin "2") (pinfunction "2_2") (pintype "passive"))
      (node (ref "R35") (pin "2") (pinfunction "2_2") (pintype "passive"))
      (node (ref "R37") (pin "2") (pinfunction "2_2") (pintype "passive"))
      (node (ref "R4") (pin "2") (pinfunction "2_2") (pintype "passive"))
      (node (ref "R43") (pin "2") (pinfunction "2_2") (pintype "passive"))
      (node (ref "R9") (pin "2") (pinfunction "2_2") (pintype "passive"))
      (node (ref "RP1") (pin "5") (pinfunction "5_5") (pintype "passive"))
      (node (ref "RP1") (pin "6") (pinfunction "6_6") (pintype "passive"))
      (node (ref "RP1") (pin "7") (pinfunction "7_7") (pintype "passive"))
      (node (ref "RP1") (pin "8") (pinfunction "8_8") (pintype "passive"))
      (node (ref "U1") (pin "2") (pinfunction "Gnd_2") (pintype "passive"))
      (node (ref "U10") (pin "10") (pinfunction "VSSM1_10") (pintype "passive"))
      (node (ref "U10") (pin "132") (pinfunction "VSSX1_132") (pintype "passive"))
      (node (ref "U10") (pin "20") (pinfunction "VSSM2_20") (pintype "passive"))
      (node (ref "U10") (pin "30") (pinfunction "VSSM3_30") (pintype "passive"))
      (node (ref "U10") (pin "49") (pinfunction "VSS2_49") (pintype "passive"))
      (node (ref "U10") (pin "52") (pinfunction "VSSX2_52") (pintype "passive"))
      (node (ref "U10") (pin "57") (pinfunction "VSSPLL_57") (pintype "passive"))
      (node (ref "U10") (pin "60") (pinfunction "TEST_60") (pintype "passive"))
      (node (ref "U10") (pin "76") (pinfunction "VSSA_76") (pintype "passive"))
      (node (ref "U10") (pin "77") (pinfunction "VRL_77") (pintype "passive"))
      (node (ref "U10") (pin "97") (pinfunction "VSS1_97") (pintype "passive"))
      (node (ref "U11") (pin "3") (pinfunction "C_3") (pintype "passive"))
      (node (ref "U13") (pin "2") (pinfunction "GND_2") (pintype "passive"))
      (node (ref "U2") (pin "2") (pinfunction "Gnd_2") (pintype "passive"))
      (node (ref "U21") (pin "5") (pinfunction "GND_5") (pintype "passive"))
      (node (ref "U6") (pin "3") (pinfunction "GND_3") (pintype "passive"))
      (node (ref "U7") (pin "4") (pinfunction "Vss_4") (pintype "passive"))
      (node (ref "U8") (pin "1") (pinfunction "A0_1") (pintype "passive"))
      (node (ref "U8") (pin "2") (pinfunction "A1_2") (pintype "passive"))
      (node (ref "U8") (pin "3") (pinfunction "A2_3") (pintype "passive"))
      (node (ref "U8") (pin "4") (pinfunction "GND_4") (pintype "passive"))
      (node (ref "U8") (pin "7") (pinfunction "WP_7") (pintype "passive"))
    )
    (net (code "105") (name "Net-(BT1-+)") (class "Default")
      (node (ref "BT1") (pin "1") (pinfunction "+_1") (pintype "passive"))
      (node (ref "U7") (pin "3") (pinfunction "VBAT_3") (pintype "passive"))
    )
    (net (code "106") (name "Net-(C7-Pad1)") (class "Default")
      (node (ref "C7") (pin "1") (pinfunction "1_1") (pintype "passive"))
      (node (ref "R12") (pin "1") (pinfunction "1_1") (pintype "passive"))
    )
    (net (code "107") (name "Net-(C8-Pad1)") (class "Default")
      (node (ref "C8") (pin "1") (pinfunction "1_1") (pintype "passive"))
      (node (ref "R13") (pin "1") (pinfunction "1_1") (pintype "passive"))
    )
    (net (code "108") (name "Net-(C52-Pad2)") (class "Default")
      (node (ref "C52") (pin "2") (pinfunction "2_2") (pintype "passive"))
      (node (ref "C98") (pin "1") (pinfunction "1_1") (pintype "passive"))
      (node (ref "R54") (pin "2") (pinfunction "2_2") (pintype "passive"))
    )
    (net (code "109") (name "Net-(C201-Pad1)") (class "Default")
      (node (ref "C201") (pin "1") (pinfunction "1_1") (pintype "passive"))
      (node (ref "R210") (pin "2") (pinfunction "2_2") (pintype "passive"))
      (node (ref "R211") (pin "1") (pinfunction "1_1") (pintype "passive"))
    )
    (net (code "110") (name "Net-(C202-Pad1)") (class "Default")
      (node (ref "C202") (pin "1") (pinfunction "1_1") (pintype "passive"))
      (node (ref "R212") (pin "2") (pinfunction "2_2") (pintype "passive"))
      (node (ref "R213") (pin "1") (pinfunction "1_1") (pintype "passive"))
    )
    (net (code "111") (name "Net-(C205-Pad1)") (class "Default")
      (node (ref "C205") (pin "1") (pinfunction "1_1") (pintype "passive"))
      (node (ref "R232") (pin "1") (pinfunction "1_1") (pintype "passive"))
      (node (ref "R233") (pin "1") (pinfunction "1_1") (pintype "passive"))
    )
    (net (code "112") (name "Net-(C206-Pad1)") (class "Default")
      (node (ref "C206") (pin "1") (pinfunction "1_1") (pintype "passive"))
      (node (ref "R231") (pin "1") (pinfunction "1_1") (pintype "passive"))
      (node (ref "R234") (pin "2") (pinfunction "2_2") (pintype "passive"))
    )
    (net (code "113") (name "Net-(D201-Pad3)") (class "Default")
      (node (ref "D201") (pin "3") (pintype "passive"))
      (node (ref "JV01") (pin "2") (pinfunction "2_2") (pintype "passive"))
      (node (ref "R210") (pin "1") (pinfunction "1_1") (pintype "passive"))
      (node (ref "TP141") (pin "1") (pinfunction "1_1") (pintype "passive"))
    )
    (net (code "114") (name "Net-(D202-Pad3)") (class "Default")
      (node (ref "D202") (pin "3") (pintype "passive"))
      (node (ref "JV02") (pin "2") (pinfunction "2_2") (pintype "passive"))
      (node (ref "R212") (pin "1") (pinfunction "1_1") (pintype "passive"))
      (node (ref "TP142") (pin "1") (pinfunction "1_1") (pintype "passive"))
    )
    (net (code "115") (name "Net-(J2-Pad2)") (class "Default")
      (node (ref "J2") (pin "2") (pinfunction "2_2") (pintype "passive"))
      (node (ref "R138") (pin "1") (pinfunction "1_1") (pintype "passive"))
      (node (ref "TP20") (pin "1") (pinfunction "1_1") (pintype "passive"))
    )
    (net (code "116") (name "Net-(J2-Pad3)") (class "Default")
      (node (ref "J2") (pin "3") (pinfunction "3_3") (pintype "passive"))
      (node (ref "R148") (pin "1") (pinfunction "1_1") (pintype "passive"))
      (node (ref "TP21") (pin "1") (pinfunction "1_1") (pintype "passive"))
    )
    (net (code "117") (name "Net-(J2-Pad4)") (class "Default")
      (node (ref "J2") (pin "4") (pinfunction "4_4") (pintype "passive"))
      (node (ref "R149") (pin "1") (pinfunction "1_1") (pintype "passive"))
      (node (ref "TP22") (pin "1") (pinfunction "1_1") (pintype "passive"))
    )
    (net (code "118") (name "Net-(J2-Pad5)") (class "Default")
      (node (ref "J2") (pin "5") (pinfunction "5_5") (pintype "passive"))
      (node (ref "R152") (pin "1") (pinfunction "1_1") (pintype "passive"))
      (node (ref "TP23") (pin "1") (pinfunction "1_1") (pintype "passive"))
    )
    (net (code "119") (name "Net-(J2-Pad6)") (class "Default")
      (node (ref "J2") (pin "6") (pinfunction "6_6") (pintype "passive"))
      (node (ref "R153") (pin "1") (pinfunction "1_1") (pintype "passive"))
      (node (ref "TP24") (pin "1") (pinfunction "1_1") (pintype "passive"))
    )
    (net (code "120") (name "Net-(J2-Pad7)") (class "Default")
      (node (ref "J2") (pin "7") (pinfunction "7_7") (pintype "passive"))
      (node (ref "R154") (pin "1") (pinfunction "1_1") (pintype "passive"))
      (node (ref "TP25") (pin "1") (pinfunction "1_1") (pintype "passive"))
    )
    (net (code "121") (name "Net-(J2-Pad8)") (class "Default")
      (node (ref "J2") (pin "8") (pinfunction "8_8") (pintype "passive"))
      (node (ref "R155") (pin "1") (pinfunction "1_1") (pintype "passive"))
      (node (ref "TP26") (pin "1") (pinfunction "1_1") (pintype "passive"))
    )
    (net (code "122") (name "Net-(J2-Pad9)") (class "Default")
      (node (ref "J2") (pin "9") (pinfunction "9_9") (pintype "passive"))
      (node (ref "R156") (pin "1") (pinfunction "1_1") (pintype "passive"))
      (node (ref "TP27") (pin "1") (pinfunction "1_1") (pintype "passive"))
    )
    (net (code "123") (name "Net-(U2-Vref)") (class "Default")
      (node (ref "C4") (pin "1") (pinfunction "1_1") (pintype "passive"))
      (node (ref "U2") (pin "5") (pinfunction "Vref_5") (pintype "passive"))
    )
    (net (code "124") (name "Net-(U6-PFI)") (class "Default")
      (node (ref "R35") (pin "1") (pinfunction "1_1") (pintype "passive"))
      (node (ref "U6") (pin "4") (pinfunction "PFI_4") (pintype "passive"))
    )
    (net (code "125") (name "Net-(U6-~{MR})") (class "Default")
      (node (ref "R33") (pin "1") (pinfunction "1_1") (pintype "passive"))
      (node (ref "U6") (pin "1") (pinfunction "~{MR}_1") (pintype "passive"))
      (node (ref "U6") (pin "8") (pinfunction "~{WDO}_8") (pintype "passive"))
    )
    (net (code "126") (name "Net-(U6-~{REST})") (class "Default")
      (node (ref "R34") (pin "1") (pinfunction "1_1") (pintype "passive"))
      (node (ref "U6") (pin "7") (pinfunction "~{REST}_7") (pintype "passive"))
    )
    (net (code "127") (name "Net-(U7-TRQ)") (class "Default")
      (node (ref "RP3") (pin "2") (pinfunction "2_2") (pintype "passive"))
      (node (ref "U7") (pin "7") (pinfunction "TRQ_7") (pintype "passive"))
    )
    (net (code "128") (name "Net-(U7-XI)") (class "Default")
      (node (ref "U7") (pin "1") (pinfunction "XI_1") (pintype "passive"))
      (node (ref "YC2") (pin "2") (pinfunction "2_2") (pintype "passive"))
    )
    (net (code "129") (name "Net-(U7-XO)") (class "Default")
      (node (ref "U7") (pin "2") (pinfunction "XO_2") (pintype "passive"))
      (node (ref "YC2") (pin "1") (pinfunction "1_1") (pintype "passive"))
    )
    (net (code "130") (name "Net-(U10-AN13{slash}PL5)") (class "Default")
      (node (ref "R139") (pin "2") (pinfunction "2_2") (pintype "passive"))
      (node (ref "U10") (pin "2") (pinfunction "AN13/PL5_2") (pintype "passive"))
    )
    (net (code "131") (name "Net-(U10-EXTAL)") (class "Default")
      (node (ref "R53") (pin "2") (pinfunction "2_2") (pintype "passive"))
      (node (ref "U10") (pin "58") (pinfunction "EXTAL_58") (pintype "passive"))
    )
    (net (code "132") (name "Net-(U10-KWAD0{slash}AD0)") (class "Default")
      (node (ref "U10") (pin "80") (pinfunction "KWAD0/AD0_80") (pintype "passive"))
      (node (ref "U11") (pin "2") (pinfunction "B_2") (pintype "input"))
    )
    (net (code "133") (name "Net-(U10-KWAD6{slash}AD6)") (class "Default")
      (node (ref "R10") (pin "1") (pinfunction "1_1") (pintype "passive"))
      (node (ref "U10") (pin "86") (pinfunction "KWAD6/AD6_86") (pintype "passive"))
    )
    (net (code "134") (name "Net-(U10-KWAD7{slash}AD7)") (class "Default")
      (node (ref "R9") (pin "1") (pinfunction "1_1") (pintype "passive"))
      (node (ref "U10") (pin "87") (pinfunction "KWAD7/AD7_87") (pintype "passive"))
    )
    (net (code "135") (name "Net-(U10-M4C0M)") (class "Default")
      (node (ref "CP14") (pin "5") (pinfunction "5_5") (pintype "passive"))
      (node (ref "RP12") (pin "4") (pinfunction "4_4") (pintype "input"))
      (node (ref "U10") (pin "5") (pinfunction "M4C0M_5") (pintype "passive"))
    )
    (net (code "136") (name "Net-(U10-M4C0P)") (class "Default")
      (node (ref "CP14") (pin "6") (pinfunction "6_6") (pintype "passive"))
      (node (ref "RP12") (pin "3") (pinfunction "3_3") (pintype "input"))
      (node (ref "U10") (pin "6") (pinfunction "M4C0P_6") (pintype "passive"))
    )
    (net (code "137") (name "Net-(U10-M4C1M)") (class "Default")
      (node (ref "CP14") (pin "7") (pinfunction "7_7") (pintype "passive"))
      (node (ref "RP12") (pin "2") (pinfunction "2_2") (pintype "input"))
      (node (ref "U10") (pin "7") (pinfunction "M4C1M_7") (pintype "passive"))
    )
    (net (code "138") (name "Net-(U10-M4C1P)") (class "Default")
      (node (ref "CP14") (pin "8") (pinfunction "8_8") (pintype "passive"))
      (node (ref "RP12") (pin "1") (pinfunction "1_1") (pintype "input"))
      (node (ref "U10") (pin "8") (pinfunction "M4C1P_8") (pintype "passive"))
    )
    (net (code "139") (name "Net-(U10-M5C0M)") (class "Default")
      (node (ref "CP13") (pin "5") (pinfunction "5_5") (pintype "passive"))
      (node (ref "RP11") (pin "4") (pinfunction "4_4") (pintype "input"))
      (node (ref "U10") (pin "31") (pinfunction "M5C0M_31") (pintype "passive"))
    )
    (net (code "140") (name "Net-(U10-M5C0P)") (class "Default")
      (node (ref "CP13") (pin "6") (pinfunction "6_6") (pintype "passive"))
      (node (ref "RP11") (pin "3") (pinfunction "3_3") (pintype "input"))
      (node (ref "U10") (pin "32") (pinfunction "M5C0P_32") (pintype "passive"))
    )
    (net (code "141") (name "Net-(U10-M5C1M)") (class "Default")
      (node (ref "CP13") (pin "7") (pinfunction "7_7") (pintype "passive"))
      (node (ref "RP11") (pin "2") (pinfunction "2_2") (pintype "input"))
      (node (ref "U10") (pin "33") (pinfunction "M5C1M_33") (pintype "passive"))
    )
    (net (code "142") (name "Net-(U10-M5C1P)") (class "Default")
      (node (ref "CP13") (pin "8") (pinfunction "8_8") (pintype "passive"))
      (node (ref "RP11") (pin "1") (pinfunction "1_1") (pintype "input"))
      (node (ref "U10") (pin "34") (pinfunction "M5C1P_34") (pintype "passive"))
    )
    (net (code "143") (name "Net-(U10-PA0{slash}FP8)") (class "Default")
      (node (ref "RP2") (pin "6") (pinfunction "6_6") (pintype "passive"))
      (node (ref "U10") (pin "111") (pinfunction "PA0/FP8_111") (pintype "passive"))
    )
    (net (code "144") (name "Net-(U10-PA1{slash}FP9)") (class "Default")
      (node (ref "RP2") (pin "5") (pinfunction "5_5") (pintype "passive"))
      (node (ref "U10") (pin "112") (pinfunction "PA1/FP9_112") (pintype "passive"))
    )
    (net (code "145") (name "Net-(U10-PA2{slash}FP10)") (class "Default")
      (node (ref "RP4") (pin "8") (pinfunction "8_8") (pintype "passive"))
      (node (ref "U10") (pin "113") (pinfunction "PA2/FP10_113") (pintype "passive"))
    )
    (net (code "146") (name "Net-(U10-PA3{slash}FP11)") (class "Default")
      (node (ref "RP4") (pin "7") (pinfunction "7_7") (pintype "passive"))
      (node (ref "U10") (pin "114") (pinfunction "PA3/FP11_114") (pintype "passive"))
    )
    (net (code "147") (name "Net-(U10-PA4{slash}FP12)") (class "Default")
      (node (ref "RP4") (pin "6") (pinfunction "6_6") (pintype "passive"))
      (node (ref "U10") (pin "115") (pinfunction "PA4/FP12_115") (pintype "passive"))
    )
    (net (code "148") (name "Net-(U10-PA5{slash}FP13)") (class "Default")
      (node (ref "RP4") (pin "5") (pinfunction "5_5") (pintype "passive"))
      (node (ref "U10") (pin "116") (pinfunction "PA5/FP13_116") (pintype "passive"))
    )
    (net (code "149") (name "Net-(U10-PA6{slash}FP14)") (class "Default")
      (node (ref "RP28") (pin "8") (pinfunction "8_8") (pintype "passive"))
      (node (ref "U10") (pin "117") (pinfunction "PA6/FP14_117") (pintype "passive"))
    )
    (net (code "150") (name "Net-(U10-PA7{slash}FP15)") (class "Default")
      (node (ref "RP28") (pin "7") (pinfunction "7_7") (pintype "passive"))
      (node (ref "U10") (pin "118") (pinfunction "PA7/FP15_118") (pintype "passive"))
    )
    (net (code "151") (name "Net-(U10-PB6{slash}FP6)") (class "Default")
      (node (ref "RP2") (pin "8") (pinfunction "8_8") (pintype "passive"))
      (node (ref "U10") (pin "109") (pinfunction "PB6/FP6_109") (pintype "passive"))
    )
    (net (code "152") (name "Net-(U10-PB7{slash}FP7)") (class "Default")
      (node (ref "RP2") (pin "7") (pinfunction "7_7") (pintype "passive"))
      (node (ref "U10") (pin "110") (pinfunction "PB7/FP7_110") (pintype "passive"))
    )
    (net (code "153") (name "Net-(U10-PC0{slash}DAT8)") (class "Default")
      (node (ref "RP30") (pin "6") (pinfunction "6_6") (pintype "passive"))
      (node (ref "U10") (pin "123") (pinfunction "PC0/DAT8_123") (pintype "passive"))
    )
    (net (code "154") (name "Net-(U10-PC1{slash}DAT9)") (class "Default")
      (node (ref "RP30") (pin "5") (pinfunction "5_5") (pintype "passive"))
      (node (ref "U10") (pin "124") (pinfunction "PC1/DAT9_124") (pintype "passive"))
    )
    (net (code "155") (name "Net-(U10-PC2{slash}DAT10)") (class "Default")
      (node (ref "RP27") (pin "8") (pinfunction "8_8") (pintype "passive"))
      (node (ref "U10") (pin "125") (pinfunction "PC2/DAT10_125") (pintype "passive"))
    )
    (net (code "156") (name "Net-(U10-PC3{slash}DAT11)") (class "Default")
      (node (ref "RP27") (pin "7") (pinfunction "7_7") (pintype "passive"))
      (node (ref "U10") (pin "126") (pinfunction "PC3/DAT11_126") (pintype "passive"))
    )
    (net (code "157") (name "Net-(U10-PC4{slash}DAT12)") (class "Default")
      (node (ref "RP14") (pin "5") (pinfunction "5_5") (pintype "passive"))
      (node (ref "U10") (pin "133") (pinfunction "PC4/DAT12_133") (pintype "passive"))
    )
    (net (code "158") (name "Net-(U10-PE0{slash}~{XIRQ})") (class "Default")
      (node (ref "RP1") (pin "1") (pinfunction "1_1") (pintype "passive"))
      (node (ref "U10") (pin "75") (pinfunction "PE0/~{XIRQ}_75") (pintype "passive"))
    )
    (net (code "159") (name "Net-(U10-PE2{slash}R{slash}~{W})") (class "Default")
      (node (ref "RP27") (pin "6") (pinfunction "6_6") (pintype "passive"))
      (node (ref "U10") (pin "127") (pinfunction "PE2/R/~{W}_127") (pintype "passive"))
    )
    (net (code "160") (name "Net-(U10-PE3{slash}~{LSTRB}{slash}LDS)") (class "Default")
      (node (ref "RP27") (pin "5") (pinfunction "5_5") (pintype "passive"))
      (node (ref "U10") (pin "128") (pinfunction "PE3/~{LSTRB}/LDS_128") (pintype "passive"))
    )
    (net (code "161") (name "Net-(U10-PE6{slash}MODB)") (class "Default")
      (node (ref "RP1") (pin "2") (pinfunction "2_2") (pintype "passive"))
      (node (ref "U10") (pin "73") (pinfunction "PE6/MODB_73") (pintype "passive"))
    )
    (net (code "162") (name "Net-(U10-PE7{slash}ECLKX2{slash}XCLKS)") (class "Default")
      (node (ref "RP14") (pin "8") (pinfunction "8_8") (pintype "passive"))
      (node (ref "U10") (pin "129") (pinfunction "PE7/ECLKX2/XCLKS_129") (pintype "passive"))
    )
    (net (code "163") (name "Net-(U10-PK7{slash}~{EWAIT}{slash}ROMCTL)") (class "Default")
      (node (ref "RP14") (pin "7") (pinfunction "7_7") (pintype "passive"))
      (node (ref "U10") (pin "130") (pinfunction "PK7/~{EWAIT}/ROMCTL_130") (pintype "passive"))
    )
    (net (code "164") (name "Net-(U10-PL0{slash}FP16)") (class "Default")
      (node (ref "RP28") (pin "6") (pinfunction "6_6") (pintype "passive"))
      (node (ref "U10") (pin "119") (pinfunction "PL0/FP16_119") (pintype "passive"))
    )
    (net (code "165") (name "Net-(U10-PL1{slash}FP17)") (class "Default")
      (node (ref "RP28") (pin "5") (pinfunction "5_5") (pintype "passive"))
      (node (ref "U10") (pin "120") (pinfunction "PL1/FP17_120") (pintype "passive"))
    )
    (net (code "166") (name "Net-(U10-PL2{slash}FP18)") (class "Default")
      (node (ref "RP30") (pin "8") (pinfunction "8_8") (pintype "passive"))
      (node (ref "U10") (pin "121") (pinfunction "PL2/FP18_121") (pintype "passive"))
    )
    (net (code "167") (name "Net-(U10-PL3{slash}FP19)") (class "Default")
      (node (ref "RP30") (pin "7") (pinfunction "7_7") (pintype "passive"))
      (node (ref "U10") (pin "122") (pinfunction "PL3/FP19_122") (pintype "passive"))
    )
    (net (code "168") (name "Net-(U10-SDA1{slash}PWM6)") (class "Default")
      (node (ref "R43") (pin "1") (pinfunction "1_1") (pintype "passive"))
      (node (ref "U10") (pin "41") (pinfunction "SDA1/PWM6_41") (pintype "passive"))
    )
    (net (code "169") (name "Net-(U10-TXD1{slash}PWM0)") (class "Default")
      (node (ref "R175") (pin "1") (pinfunction "1_1") (pintype "passive"))
      (node (ref "U10") (pin "39") (pinfunction "TXD1/PWM0_39") (pintype "passive"))
    )
    (net (code "170") (name "Net-(U10-VDD1)") (class "Default")
      (node (ref "C34") (pin "1") (pinfunction "1_1") (pintype "passive"))
      (node (ref "U10") (pin "96") (pinfunction "VDD1_96") (pintype "passive"))
    )
    (net (code "171") (name "Net-(U10-VDDPLL)") (class "Default")
      (node (ref "C48") (pin "2") (pinfunction "2_2") (pintype "passive"))
      (node (ref "C52") (pin "1") (pinfunction "1_1") (pintype "passive"))
      (node (ref "U10") (pin "55") (pinfunction "VDDPLL_55") (pintype "passive"))
    )
    (net (code "172") (name "Net-(U10-XFC)") (class "Default")
      (node (ref "C48") (pin "1") (pinfunction "1_1") (pintype "passive"))
      (node (ref "R54") (pin "1") (pinfunction "1_1") (pintype "passive"))
      (node (ref "U10") (pin "56") (pinfunction "XFC_56") (pintype "passive"))
    )
    (net (code "173") (name "Net-(U10-~{IRQ}{slash}PE1)") (class "Default")
      (node (ref "R142") (pin "1") (pinfunction "1_1") (pintype "passive"))
      (node (ref "U10") (pin "72") (pinfunction "~{IRQ}/PE1_72") (pintype "passive"))
    )
    (net (code "174") (name "Net-(U13-OUT)") (class "Default")
      (node (ref "R53") (pin "1") (pinfunction "1_1") (pintype "passive"))
      (node (ref "U13") (pin "3") (pinfunction "OUT_3") (pintype "passive"))
    )
    (net (code "175") (name "Net-(U21-OUT1)") (class "Default")
      (node (ref "R233") (pin "2") (pinfunction "2_2") (pintype "passive"))
      (node (ref "U21") (pin "8") (pinfunction "OUT1_8") (pintype "passive"))
    )
    (net (code "176") (name "Net-(U21-OUT2)") (class "Default")
      (node (ref "R234") (pin "1") (pinfunction "1_1") (pintype "passive"))
      (node (ref "U21") (pin "7") (pinfunction "OUT2_7") (pintype "passive"))
    )
    (net (code "177") (name "Net-(U21-VCC)") (class "Default")
      (node (ref "C208") (pin "1") (pinfunction "1_1") (pintype "passive"))
      (node (ref "CP200") (pin "1") (pinfunction "1_1") (pintype "passive"))
      (node (ref "L205") (pin "2") (pinfunction "2_2") (pintype "passive"))
      (node (ref "U21") (pin "4") (pinfunction "VCC_4") (pintype "passive"))
    )
    (net (code "178") (name "unconnected-(DZ6-Pad5)") (class "Default")
      (node (ref "DZ6") (pin "5") (pintype "passive"))
    )
    (net (code "179") (name "unconnected-(J1-Pad2)") (class "Default")
      (node (ref "J1") (pin "2") (pinfunction "2_2") (pintype "passive"))
    )
    (net (code "180") (name "unconnected-(J1-Pad3)") (class "Default")
      (node (ref "J1") (pin "3") (pinfunction "3_3") (pintype "passive"))
    )
    (net (code "181") (name "unconnected-(J2-Pad15)") (class "Default")
      (node (ref "J2") (pin "15") (pinfunction "15_15") (pintype "passive"))
    )
    (net (code "182") (name "unconnected-(J2-Pad17)") (class "Default")
      (node (ref "J2") (pin "17") (pinfunction "17_17") (pintype "passive"))
    )
    (net (code "183") (name "unconnected-(RP1-Pad4)") (class "Default")
      (node (ref "RP1") (pin "4") (pinfunction "4_4") (pintype "passive"))
    )
    (net (code "184") (name "unconnected-(RP3-Pad1)") (class "Default")
      (node (ref "RP3") (pin "1") (pinfunction "1_1") (pintype "passive"))
    )
    (net (code "185") (name "unconnected-(RP14-Pad6)") (class "Default")
      (node (ref "RP14") (pin "6") (pinfunction "6_6") (pintype "passive"))
    )
    (net (code "186") (name "unconnected-(U6-~{PFO}-Pad5)") (class "Default")
      (node (ref "U6") (pin "5") (pinfunction "~{PFO}_5") (pintype "passive+no_connect"))
    )
    (net (code "187") (name "unconnected-(U10-XTAL-Pad59)") (class "Default")
      (node (ref "U10") (pin "59") (pinfunction "XTAL_59") (pintype "passive+no_connect"))
    )
    (net (code "188") (name "unconnected-(U13-OE-Pad1)") (class "Default")
      (node (ref "U13") (pin "1") (pinfunction "OE_1") (pintype "passive+no_connect"))
    )
    (net (code "189") (name "unconnected-(U21-IN3-Pad3)") (class "Default")
      (node (ref "U21") (pin "3") (pinfunction "IN3_3") (pintype "passive"))
    )
    (net (code "190") (name "unconnected-(U21-OUT3-Pad6)") (class "Default")
      (node (ref "U21") (pin "6") (pinfunction "OUT3_6") (pintype "passive"))
    )
  )
)
